# SCH_CJ4_Electrical_Panel.net
KiCad netlist of a schematic drawn in EasyEDA
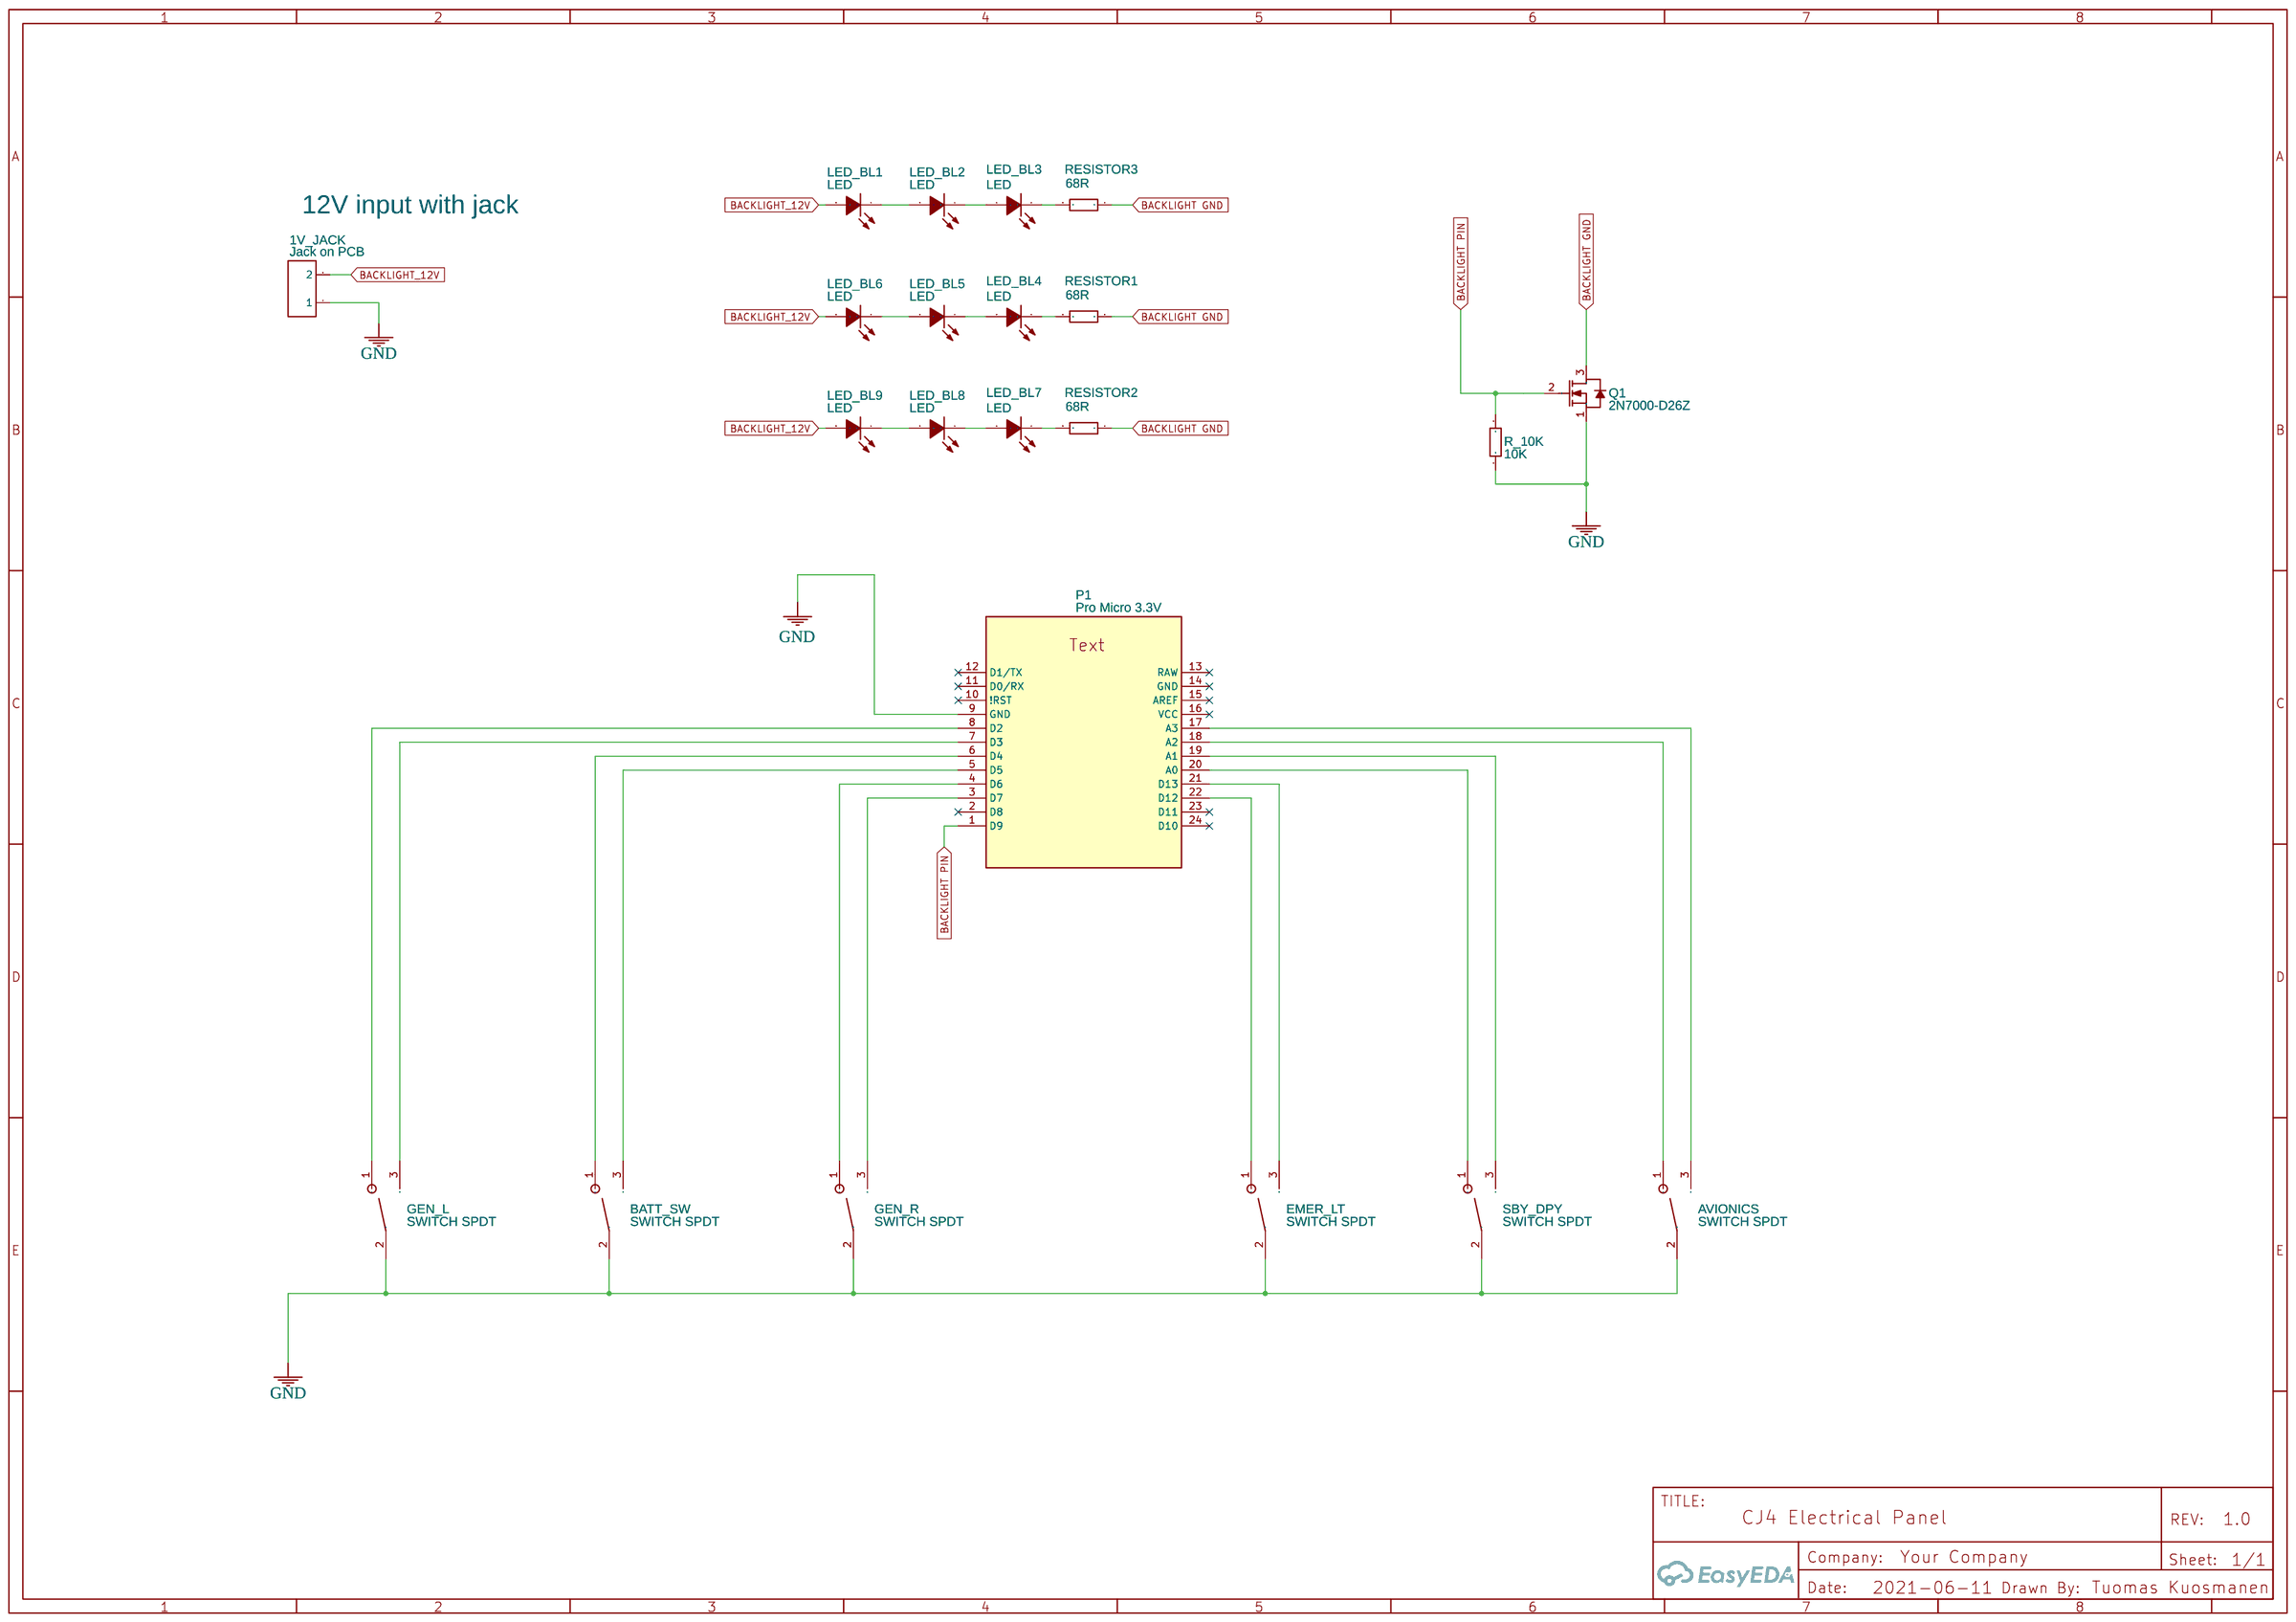
[diagram p0: schematic sheet]

(export (version "E")
  (design (tool "Eeschema 10.0.6"))
  (components
    (comp (ref "1V_JACK") (value "Jack on PCB") (libsource (lib "") (part "J-Header-Male-2.54_1x2")))
    (comp (ref "AVIONICS")
      (value "SWITCH SPDT")
      (fields
        (field (name "BOM_Manufacturer Part") "200MSP1T1B1M2QEH")
        (field (name "BOM_Supplier Part") "C273365")
      )
      (libsource (lib "") (part "SWITCH SPDT_2"))
    )
    (comp (ref "BATT_SW")
      (value "SWITCH SPDT")
      (fields
        (field (name "BOM_Manufacturer Part") "200MSP1T1B1M2QEH")
        (field (name "BOM_Supplier Part") "C273365")
      )
      (libsource (lib "") (part "SWITCH SPDT"))
    )
    (comp (ref "EMER_LT")
      (value "SWITCH SPDT")
      (fields
        (field (name "BOM_Manufacturer Part") "200MSP1T1B1M2QEH")
        (field (name "BOM_Supplier Part") "C273365")
      )
      (libsource (lib "") (part "SWITCH SPDT_4"))
    )
    (comp (ref "GEN_L")
      (value "SWITCH SPDT")
      (fields
        (field (name "BOM_Manufacturer Part") "200MSP1T1B1M2QEH")
        (field (name "BOM_Supplier Part") "C273365")
      )
      (libsource (lib "") (part "SWITCH SPDT_3"))
    )
    (comp (ref "GEN_R")
      (value "SWITCH SPDT")
      (fields
        (field (name "BOM_Manufacturer Part") "200MSP1T1B1M2QEH")
        (field (name "BOM_Supplier Part") "C273365")
      )
      (libsource (lib "") (part "SWITCH SPDT_1"))
    )
    (comp (ref "LED_BL1")
      (value "LED")
      (fields
        (field (name "BOM_Manufacturer Part") "HQ17-2102UYOC")
        (field (name "BOM_Supplier Part") "C154481")
      )
      (libsource (lib "") (part "HQ17-2102UYOC"))
    )
    (comp (ref "LED_BL2")
      (value "LED")
      (fields
        (field (name "BOM_Manufacturer Part") "HQ17-2102UYOC")
        (field (name "BOM_Supplier Part") "C154481")
      )
      (libsource (lib "") (part "HQ17-2102UYOC"))
    )
    (comp (ref "LED_BL3")
      (value "LED")
      (fields
        (field (name "BOM_Manufacturer Part") "HQ17-2102UYOC")
        (field (name "BOM_Supplier Part") "C154481")
      )
      (libsource (lib "") (part "HQ17-2102UYOC"))
    )
    (comp (ref "LED_BL4")
      (value "LED")
      (fields
        (field (name "BOM_Manufacturer Part") "HQ17-2102UYOC")
        (field (name "BOM_Supplier Part") "C154481")
      )
      (libsource (lib "") (part "HQ17-2102UYOC"))
    )
    (comp (ref "LED_BL5")
      (value "LED")
      (fields
        (field (name "BOM_Manufacturer Part") "HQ17-2102UYOC")
        (field (name "BOM_Supplier Part") "C154481")
      )
      (libsource (lib "") (part "HQ17-2102UYOC"))
    )
    (comp (ref "LED_BL6")
      (value "LED")
      (fields
        (field (name "BOM_Manufacturer Part") "HQ17-2102UYOC")
        (field (name "BOM_Supplier Part") "C154481")
      )
      (libsource (lib "") (part "HQ17-2102UYOC"))
    )
    (comp (ref "LED_BL7")
      (value "LED")
      (fields
        (field (name "BOM_Manufacturer Part") "HQ17-2102UYOC")
        (field (name "BOM_Supplier Part") "C154481")
      )
      (libsource (lib "") (part "HQ17-2102UYOC"))
    )
    (comp (ref "LED_BL8")
      (value "LED")
      (fields
        (field (name "BOM_Manufacturer Part") "HQ17-2102UYOC")
        (field (name "BOM_Supplier Part") "C154481")
      )
      (libsource (lib "") (part "HQ17-2102UYOC"))
    )
    (comp (ref "LED_BL9")
      (value "LED")
      (fields
        (field (name "BOM_Manufacturer Part") "HQ17-2102UYOC")
        (field (name "BOM_Supplier Part") "C154481")
      )
      (libsource (lib "") (part "HQ17-2102UYOC"))
    )
    (comp (ref "P1")
      (value "Pro Micro 3.3V")
      (fields (field (name "BOM_Supplier Part") "12587"))
      (libsource (lib "") (part "Pro Micro 3.3V"))
    )
    (comp (ref "Q1")
      (value "2N7000-D26Z")
      (fields (field (name "BOM_Supplier Part") "C258193"))
      (libsource (lib "") (part "2N7000-D26Z"))
    )
    (comp (ref "RESISTOR1")
      (value "68R")
      (fields
        (field (name "BOM_Manufacturer Part") "1206W4J0331T5E")
        (field (name "BOM_Supplier Part") "C25374")
      )
      (libsource (lib "") (part "1206W4J0331T5E"))
    )
    (comp (ref "RESISTOR2")
      (value "68R")
      (fields
        (field (name "BOM_Manufacturer Part") "1206W4J0331T5E")
        (field (name "BOM_Supplier Part") "C25374")
      )
      (libsource (lib "") (part "1206W4J0331T5E"))
    )
    (comp (ref "RESISTOR3")
      (value "68R")
      (fields
        (field (name "BOM_Manufacturer Part") "1206W4J0331T5E")
        (field (name "BOM_Supplier Part") "C25374")
      )
      (libsource (lib "") (part "1206W4J0331T5E"))
    )
    (comp (ref "R_10K")
      (value "10K")
      (fields
        (field (name "BOM_Manufacturer Part") "1206W4J0331T5E")
        (field (name "BOM_Supplier Part") "C25374")
      )
      (libsource (lib "") (part "1206W4J0331T5E_1"))
    )
    (comp (ref "SBY_DPY")
      (value "SWITCH SPDT")
      (fields
        (field (name "BOM_Manufacturer Part") "200MSP1T1B1M2QEH")
        (field (name "BOM_Supplier Part") "C273365")
      )
      (libsource (lib "") (part "SWITCH SPDT_5"))
    )
  )
  (nets
    (net (code "1") (name "BACKLIGHT GND") (class "Default")
      (node (ref "Q1") (pin "3") (pinfunction "D_3") (pintype "unspecified"))
      (node (ref "RESISTOR1") (pin "1") (pinfunction "1_1") (pintype "input"))
      (node (ref "RESISTOR2") (pin "1") (pinfunction "1_1") (pintype "input"))
      (node (ref "RESISTOR3") (pin "1") (pinfunction "1_1") (pintype "input"))
    )
    (net (code "2") (name "BACKLIGHT PIN") (class "Default")
      (node (ref "P1") (pin "1") (pinfunction "D9_1") (pintype "unspecified"))
      (node (ref "Q1") (pin "2") (pinfunction "G_2") (pintype "unspecified"))
      (node (ref "R_10K") (pin "2") (pinfunction "2_2") (pintype "input"))
    )
    (net (code "3") (name "BACKLIGHT_12V") (class "Default")
      (node (ref "1V_JACK") (pin "2") (pinfunction "2_2") (pintype "unspecified"))
      (node (ref "LED_BL1") (pin "2") (pinfunction "A_2") (pintype "unspecified"))
      (node (ref "LED_BL6") (pin "2") (pinfunction "A_2") (pintype "unspecified"))
      (node (ref "LED_BL9") (pin "2") (pinfunction "A_2") (pintype "unspecified"))
    )
    (net (code "4") (name "GND") (class "Default")
      (node (ref "1V_JACK") (pin "1") (pinfunction "1_1") (pintype "unspecified"))
      (node (ref "AVIONICS") (pin "2") (pinfunction "2_2") (pintype "input"))
      (node (ref "BATT_SW") (pin "2") (pinfunction "2_2") (pintype "input"))
      (node (ref "EMER_LT") (pin "2") (pinfunction "2_2") (pintype "input"))
      (node (ref "GEN_L") (pin "2") (pinfunction "2_2") (pintype "input"))
      (node (ref "GEN_R") (pin "2") (pinfunction "2_2") (pintype "input"))
      (node (ref "P1") (pin "9") (pinfunction "GND_9") (pintype "unspecified"))
      (node (ref "Q1") (pin "1") (pinfunction "S_1") (pintype "unspecified"))
      (node (ref "R_10K") (pin "1") (pinfunction "1_1") (pintype "input"))
      (node (ref "SBY_DPY") (pin "2") (pinfunction "2_2") (pintype "input"))
    )
    (net (code "5") (name "Net-(LED_BL1-K)") (class "Default")
      (node (ref "LED_BL1") (pin "1") (pinfunction "K_1") (pintype "unspecified"))
      (node (ref "LED_BL2") (pin "2") (pinfunction "A_2") (pintype "unspecified"))
    )
    (net (code "6") (name "Net-(LED_BL2-K)") (class "Default")
      (node (ref "LED_BL2") (pin "1") (pinfunction "K_1") (pintype "unspecified"))
      (node (ref "LED_BL3") (pin "2") (pinfunction "A_2") (pintype "unspecified"))
    )
    (net (code "7") (name "Net-(LED_BL3-K)") (class "Default")
      (node (ref "LED_BL3") (pin "1") (pinfunction "K_1") (pintype "unspecified"))
      (node (ref "RESISTOR3") (pin "2") (pinfunction "2_2") (pintype "input"))
    )
    (net (code "8") (name "Net-(LED_BL4-A)") (class "Default")
      (node (ref "LED_BL4") (pin "2") (pinfunction "A_2") (pintype "unspecified"))
      (node (ref "LED_BL5") (pin "1") (pinfunction "K_1") (pintype "unspecified"))
    )
    (net (code "9") (name "Net-(LED_BL4-K)") (class "Default")
      (node (ref "LED_BL4") (pin "1") (pinfunction "K_1") (pintype "unspecified"))
      (node (ref "RESISTOR1") (pin "2") (pinfunction "2_2") (pintype "input"))
    )
    (net (code "10") (name "Net-(LED_BL5-A)") (class "Default")
      (node (ref "LED_BL5") (pin "2") (pinfunction "A_2") (pintype "unspecified"))
      (node (ref "LED_BL6") (pin "1") (pinfunction "K_1") (pintype "unspecified"))
    )
    (net (code "11") (name "Net-(LED_BL7-A)") (class "Default")
      (node (ref "LED_BL7") (pin "2") (pinfunction "A_2") (pintype "unspecified"))
      (node (ref "LED_BL8") (pin "1") (pinfunction "K_1") (pintype "unspecified"))
    )
    (net (code "12") (name "Net-(LED_BL7-K)") (class "Default")
      (node (ref "LED_BL7") (pin "1") (pinfunction "K_1") (pintype "unspecified"))
      (node (ref "RESISTOR2") (pin "2") (pinfunction "2_2") (pintype "input"))
    )
    (net (code "13") (name "Net-(LED_BL8-A)") (class "Default")
      (node (ref "LED_BL8") (pin "2") (pinfunction "A_2") (pintype "unspecified"))
      (node (ref "LED_BL9") (pin "1") (pinfunction "K_1") (pintype "unspecified"))
    )
    (net (code "14") (name "Net-(P1-A0)") (class "Default")
      (node (ref "P1") (pin "20") (pinfunction "A0_20") (pintype "unspecified"))
      (node (ref "SBY_DPY") (pin "1") (pinfunction "1_1") (pintype "input"))
    )
    (net (code "15") (name "Net-(P1-A1)") (class "Default")
      (node (ref "P1") (pin "19") (pinfunction "A1_19") (pintype "unspecified"))
      (node (ref "SBY_DPY") (pin "3") (pinfunction "3_3") (pintype "input"))
    )
    (net (code "16") (name "Net-(P1-A2)") (class "Default")
      (node (ref "AVIONICS") (pin "1") (pinfunction "1_1") (pintype "input"))
      (node (ref "P1") (pin "18") (pinfunction "A2_18") (pintype "unspecified"))
    )
    (net (code "17") (name "Net-(P1-A3)") (class "Default")
      (node (ref "AVIONICS") (pin "3") (pinfunction "3_3") (pintype "input"))
      (node (ref "P1") (pin "17") (pinfunction "A3_17") (pintype "unspecified"))
    )
    (net (code "18") (name "Net-(P1-D2)") (class "Default")
      (node (ref "GEN_L") (pin "1") (pinfunction "1_1") (pintype "input"))
      (node (ref "P1") (pin "8") (pinfunction "D2_8") (pintype "unspecified"))
    )
    (net (code "19") (name "Net-(P1-D3)") (class "Default")
      (node (ref "GEN_L") (pin "3") (pinfunction "3_3") (pintype "input"))
      (node (ref "P1") (pin "7") (pinfunction "D3_7") (pintype "unspecified"))
    )
    (net (code "20") (name "Net-(P1-D4)") (class "Default")
      (node (ref "BATT_SW") (pin "1") (pinfunction "1_1") (pintype "input"))
      (node (ref "P1") (pin "6") (pinfunction "D4_6") (pintype "unspecified"))
    )
    (net (code "21") (name "Net-(P1-D5)") (class "Default")
      (node (ref "BATT_SW") (pin "3") (pinfunction "3_3") (pintype "input"))
      (node (ref "P1") (pin "5") (pinfunction "D5_5") (pintype "unspecified"))
    )
    (net (code "22") (name "Net-(P1-D6)") (class "Default")
      (node (ref "GEN_R") (pin "1") (pinfunction "1_1") (pintype "input"))
      (node (ref "P1") (pin "4") (pinfunction "D6_4") (pintype "unspecified"))
    )
    (net (code "23") (name "Net-(P1-D7)") (class "Default")
      (node (ref "GEN_R") (pin "3") (pinfunction "3_3") (pintype "input"))
      (node (ref "P1") (pin "3") (pinfunction "D7_3") (pintype "unspecified"))
    )
    (net (code "24") (name "Net-(P1-D12)") (class "Default")
      (node (ref "EMER_LT") (pin "1") (pinfunction "1_1") (pintype "input"))
      (node (ref "P1") (pin "22") (pinfunction "D12_22") (pintype "unspecified"))
    )
    (net (code "25") (name "Net-(P1-D13)") (class "Default")
      (node (ref "EMER_LT") (pin "3") (pinfunction "3_3") (pintype "input"))
      (node (ref "P1") (pin "21") (pinfunction "D13_21") (pintype "unspecified"))
    )
    (net (code "26") (name "unconnected-(P1-!RST-Pad10)") (class "Default")
      (node (ref "P1") (pin "10") (pinfunction "!RST_10") (pintype "unspecified+no_connect"))
    )
    (net (code "27") (name "unconnected-(P1-AREF-Pad15)") (class "Default")
      (node (ref "P1") (pin "15") (pinfunction "AREF_15") (pintype "unspecified+no_connect"))
    )
    (net (code "28") (name "unconnected-(P1-D0{slash}RX-Pad11)") (class "Default")
      (node (ref "P1") (pin "11") (pinfunction "D0/RX_11") (pintype "unspecified+no_connect"))
    )
    (net (code "29") (name "unconnected-(P1-D1{slash}TX-Pad12)") (class "Default")
      (node (ref "P1") (pin "12") (pinfunction "D1/TX_12") (pintype "unspecified+no_connect"))
    )
    (net (code "30") (name "unconnected-(P1-D8-Pad2)") (class "Default")
      (node (ref "P1") (pin "2") (pinfunction "D8_2") (pintype "unspecified+no_connect"))
    )
    (net (code "31") (name "unconnected-(P1-D10-Pad24)") (class "Default")
      (node (ref "P1") (pin "24") (pinfunction "D10_24") (pintype "unspecified+no_connect"))
    )
    (net (code "32") (name "unconnected-(P1-D11-Pad23)") (class "Default")
      (node (ref "P1") (pin "23") (pinfunction "D11_23") (pintype "unspecified+no_connect"))
    )
    (net (code "33") (name "unconnected-(P1-GND-Pad14)") (class "Default")
      (node (ref "P1") (pin "14") (pinfunction "GND_14") (pintype "unspecified+no_connect"))
    )
    (net (code "34") (name "unconnected-(P1-RAW-Pad13)") (class "Default")
      (node (ref "P1") (pin "13") (pinfunction "RAW_13") (pintype "unspecified+no_connect"))
    )
    (net (code "35") (name "unconnected-(P1-VCC-Pad16)") (class "Default")
      (node (ref "P1") (pin "16") (pinfunction "VCC_16") (pintype "unspecified+no_connect"))
    )
  )
)
